# internal_excitation_-_8.net
KiCad netlist of a schematic drawn in EAGLE
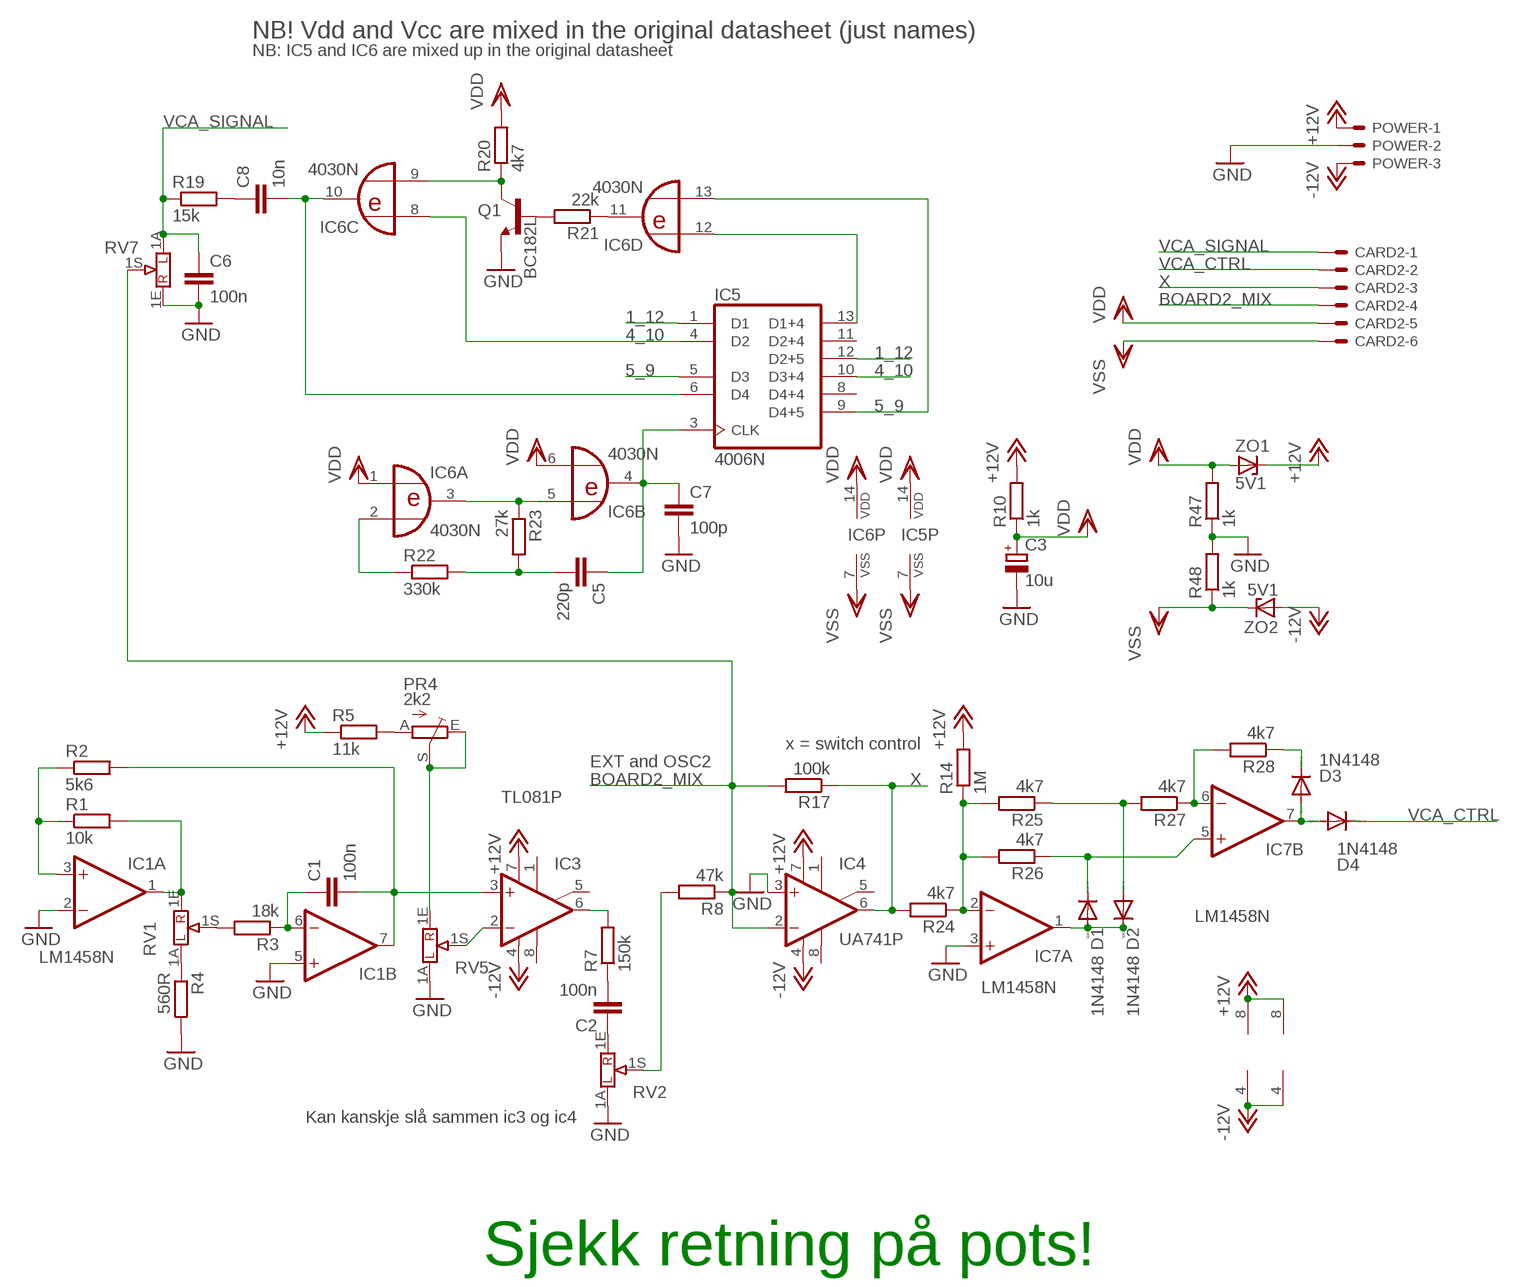
[diagram p0: schematic, sheet 1]

(export (version "E")
  (design (tool "Eeschema 10.0.6"))
  (components
    (comp (ref "C1")
      (value "100n")
      (footprint "eagle-import:C050-025X075")
      (libsource (lib "eagle-import") (part "C-EU050-025X075"))
    )
    (comp (ref "C2")
      (value "100n")
      (footprint "eagle-import:C025-025X050")
      (libsource (lib "eagle-import") (part "C-EU025-025X050"))
    )
    (comp (ref "C3")
      (value "10u")
      (footprint "eagle-import:E2,5-5")
      (libsource (lib "eagle-import") (part "CPOL-EUE2.5-5"))
    )
    (comp (ref "C5")
      (value "220p")
      (footprint "eagle-import:C025-025X050")
      (libsource (lib "eagle-import") (part "C-EU025-025X050"))
    )
    (comp (ref "C6")
      (value "100n")
      (footprint "eagle-import:C025-025X050")
      (libsource (lib "eagle-import") (part "C-EU025-025X050"))
    )
    (comp (ref "C7")
      (value "100p")
      (footprint "eagle-import:C025-025X050")
      (libsource (lib "eagle-import") (part "C-EU025-025X050"))
    )
    (comp (ref "C8")
      (value "10n")
      (footprint "eagle-import:C050-025X075")
      (libsource (lib "eagle-import") (part "C-EU050-025X075"))
    )
    (comp (ref "CARD2")
      (value "22-23-2061")
      (footprint "eagle-import:22-23-2061")
      (fields (field (name "MF") "MOLEX"))
      (libsource (lib "eagle-import") (part "22-23-2061"))
    )
    (comp (ref "D1")
      (value "1N4148")
      (footprint "eagle-import:DO35-5J")
      (libsource (lib "eagle-import") (part "1N4148DOJ35-5"))
    )
    (comp (ref "D2")
      (value "1N4148")
      (footprint "eagle-import:DO35-5J")
      (libsource (lib "eagle-import") (part "1N4148DOJ35-5"))
    )
    (comp (ref "D3")
      (value "1N4148")
      (footprint "eagle-import:DO35-5J")
      (libsource (lib "eagle-import") (part "1N4148DOJ35-5"))
    )
    (comp (ref "D4")
      (value "1N4148")
      (footprint "eagle-import:DO35-5J")
      (libsource (lib "eagle-import") (part "1N4148DOJ35-5"))
    )
    (comp (ref "IC1")
      (value "LM1458N")
      (footprint "eagle-import:DIL08")
      (libsource (lib "eagle-import") (part "1458NLM"))
    )
    (comp (ref "IC3")
      (value "TL081P")
      (footprint "eagle-import:DIL08")
      (libsource (lib "eagle-import") (part "TL081P"))
    )
    (comp (ref "IC4")
      (value "UA741P")
      (footprint "eagle-import:DIL08")
      (libsource (lib "eagle-import") (part "741PUA"))
    )
    (comp (ref "IC5")
      (value "4006N")
      (footprint "eagle-import:DIL14")
      (libsource (lib "eagle-import") (part "4006N"))
    )
    (comp (ref "IC6")
      (value "4030N")
      (footprint "eagle-import:DIL14")
      (libsource (lib "eagle-import") (part "4030N"))
    )
    (comp (ref "IC7")
      (value "LM1458N")
      (footprint "eagle-import:DIL08")
      (libsource (lib "eagle-import") (part "1458NLM"))
    )
    (comp (ref "POWER")
      (value "KK-156-3")
      (footprint "eagle-import:KK-156-3")
      (libsource (lib "eagle-import") (part "KK-156-3"))
    )
    (comp (ref "PR4")
      (value "2k2")
      (footprint "eagle-import:CA9V")
      (libsource (lib "eagle-import") (part "TRIM_EU-CA9V"))
    )
    (comp (ref "Q1")
      (value "BC182L")
      (footprint "eagle-import:TO92-ECB")
      (libsource (lib "eagle-import") (part "-NPN-TO92-ECB"))
    )
    (comp (ref "R1")
      (value "10k")
      (footprint "eagle-import:0207_7")
      (libsource (lib "eagle-import") (part "R-EU_0207/7"))
    )
    (comp (ref "R2")
      (value "5k6")
      (footprint "eagle-import:0207_7")
      (libsource (lib "eagle-import") (part "R-EU_0207/7"))
    )
    (comp (ref "R3")
      (value "18k")
      (footprint "eagle-import:0207_7")
      (libsource (lib "eagle-import") (part "R-EU_0207/7"))
    )
    (comp (ref "R4")
      (value "560R")
      (footprint "eagle-import:0207_7")
      (libsource (lib "eagle-import") (part "R-EU_0207/7"))
    )
    (comp (ref "R5")
      (value "11k")
      (footprint "eagle-import:0207_7")
      (libsource (lib "eagle-import") (part "R-EU_0207/7"))
    )
    (comp (ref "R7")
      (value "150k")
      (footprint "eagle-import:0207_7")
      (libsource (lib "eagle-import") (part "R-EU_0207/7"))
    )
    (comp (ref "R8")
      (value "47k")
      (footprint "eagle-import:0207_7")
      (libsource (lib "eagle-import") (part "R-EU_0207/7"))
    )
    (comp (ref "R10")
      (value "1k")
      (footprint "eagle-import:0207_7")
      (libsource (lib "eagle-import") (part "R-EU_0207/7"))
    )
    (comp (ref "R14")
      (value "1M")
      (footprint "eagle-import:0207_7")
      (libsource (lib "eagle-import") (part "R-EU_0207/7"))
    )
    (comp (ref "R17")
      (value "100k")
      (footprint "eagle-import:0207_7")
      (libsource (lib "eagle-import") (part "R-EU_0207/7"))
    )
    (comp (ref "R19")
      (value "15k")
      (footprint "eagle-import:0207_7")
      (libsource (lib "eagle-import") (part "R-EU_0207/7"))
    )
    (comp (ref "R20")
      (value "4k7")
      (footprint "eagle-import:0207_7")
      (libsource (lib "eagle-import") (part "R-EU_0207/7"))
    )
    (comp (ref "R21")
      (value "22k")
      (footprint "eagle-import:0207_7")
      (libsource (lib "eagle-import") (part "R-EU_0207/7"))
    )
    (comp (ref "R22")
      (value "330k")
      (footprint "eagle-import:0207_7")
      (libsource (lib "eagle-import") (part "R-EU_0207/7"))
    )
    (comp (ref "R23")
      (value "27k")
      (footprint "eagle-import:0207_7")
      (libsource (lib "eagle-import") (part "R-EU_0207/7"))
    )
    (comp (ref "R24")
      (value "4k7")
      (footprint "eagle-import:0207_7")
      (libsource (lib "eagle-import") (part "R-EU_0207/7"))
    )
    (comp (ref "R25")
      (value "4k7")
      (footprint "eagle-import:0207_7")
      (libsource (lib "eagle-import") (part "R-EU_0207/7"))
    )
    (comp (ref "R26")
      (value "4k7")
      (footprint "eagle-import:0207_7")
      (libsource (lib "eagle-import") (part "R-EU_0207/7"))
    )
    (comp (ref "R27")
      (value "4k7")
      (footprint "eagle-import:0207_7")
      (libsource (lib "eagle-import") (part "R-EU_0207/7"))
    )
    (comp (ref "R28")
      (value "4k7")
      (footprint "eagle-import:0207_7")
      (libsource (lib "eagle-import") (part "R-EU_0207/7"))
    )
    (comp (ref "R47")
      (value "1k")
      (footprint "eagle-import:0207_7")
      (libsource (lib "eagle-import") (part "R-EU_0207/7"))
    )
    (comp (ref "R48")
      (value "1k")
      (footprint "eagle-import:0207_7")
      (libsource (lib "eagle-import") (part "R-EU_0207/7"))
    )
    (comp (ref "RV1")
      (value "10k log")
      (footprint "eagle-import:POT16_W_BRACKET")
      (libsource (lib "eagle-import") (part "POT16_W_BRACKET{dblquote}{dblquote}"))
    )
    (comp (ref "RV2")
      (value "10k log")
      (footprint "eagle-import:POT16_W_BRACKET")
      (libsource (lib "eagle-import") (part "POT16_W_BRACKET{dblquote}{dblquote}"))
    )
    (comp (ref "RV5")
      (value "10k")
      (footprint "eagle-import:POT16_W_BRACKET")
      (libsource (lib "eagle-import") (part "POT16_W_BRACKET{dblquote}{dblquote}"))
    )
    (comp (ref "RV7")
      (value "10k")
      (footprint "eagle-import:POT16_W_BRACKET")
      (libsource (lib "eagle-import") (part "POT16_W_BRACKET{dblquote}{dblquote}"))
    )
    (comp (ref "ZO1")
      (value "5V1")
      (footprint "eagle-import:ZDIO-5")
      (libsource (lib "eagle-import") (part "ZENER-DIODEZD-5"))
    )
    (comp (ref "ZO2")
      (value "5V1")
      (footprint "eagle-import:ZDIO-5")
      (libsource (lib "eagle-import") (part "ZENER-DIODEZD-5"))
    )
  )
  (nets
    (net (code "1") (name "+12V") (class "Default")
      (node (ref "IC1") (pin "8") (pinfunction "V+_8") (pintype "power_in"))
      (node (ref "IC3") (pin "7") (pinfunction "V+_7") (pintype "power_in"))
      (node (ref "IC4") (pin "7") (pinfunction "V+_7") (pintype "power_in"))
      (node (ref "IC7") (pin "8") (pinfunction "V+_8") (pintype "power_in"))
      (node (ref "POWER") (pin "1") (pinfunction "S_1") (pintype "passive"))
      (node (ref "R10") (pin "2") (pinfunction "2_2") (pintype "passive"))
      (node (ref "R14") (pin "2") (pinfunction "2_2") (pintype "passive"))
      (node (ref "R5") (pin "1") (pinfunction "1_1") (pintype "passive"))
      (node (ref "ZO1") (pin "C") (pinfunction "C_C") (pintype "passive"))
    )
    (net (code "2") (name "-12V") (class "Default")
      (node (ref "IC1") (pin "4") (pinfunction "V-_4") (pintype "power_in"))
      (node (ref "IC3") (pin "4") (pinfunction "V-_4") (pintype "power_in"))
      (node (ref "IC4") (pin "4") (pinfunction "V-_4") (pintype "power_in"))
      (node (ref "IC7") (pin "4") (pinfunction "V-_4") (pintype "power_in"))
      (node (ref "POWER") (pin "3") (pinfunction "S_3") (pintype "passive"))
      (node (ref "ZO2") (pin "A") (pinfunction "A_A") (pintype "passive"))
    )
    (net (code "3") (name "/1_12") (class "Default")
      (node (ref "IC5") (pin "1") (pinfunction "D1_1") (pintype "input"))
      (node (ref "IC5") (pin "12") (pinfunction "D2+5_12") (pintype "output"))
    )
    (net (code "4") (name "/4_10") (class "Default")
      (node (ref "IC5") (pin "10") (pinfunction "D3+4_10") (pintype "output"))
      (node (ref "IC5") (pin "4") (pinfunction "D2_4") (pintype "input"))
      (node (ref "IC6") (pin "8") (pinfunction "I0_8") (pintype "input"))
    )
    (net (code "5") (name "/5_9") (class "Default")
      (node (ref "IC5") (pin "5") (pinfunction "D3_5") (pintype "input"))
      (node (ref "IC5") (pin "9") (pinfunction "D4+5_9") (pintype "output"))
      (node (ref "IC6") (pin "13") (pinfunction "I1_13") (pintype "input"))
    )
    (net (code "6") (name "/BOARD2_MIX") (class "Default")
      (node (ref "CARD2") (pin "4") (pinfunction "S_4") (pintype "passive"))
      (node (ref "IC4") (pin "2") (pinfunction "-IN_2") (pintype "input"))
      (node (ref "R17") (pin "2") (pinfunction "2_2") (pintype "passive"))
      (node (ref "R8") (pin "1") (pinfunction "1_1") (pintype "passive"))
      (node (ref "RV7") (pin "1S") (pinfunction "1S_1S") (pintype "passive"))
    )
    (net (code "7") (name "/VCA_CTRL") (class "Default")
      (node (ref "CARD2") (pin "2") (pinfunction "S_2") (pintype "passive"))
      (node (ref "D4") (pin "C") (pinfunction "C_C") (pintype "passive"))
    )
    (net (code "8") (name "/VCA_SIGNAL") (class "Default")
      (node (ref "C6") (pin "1") (pinfunction "1_1") (pintype "passive"))
      (node (ref "CARD2") (pin "1") (pinfunction "S_1") (pintype "passive"))
      (node (ref "R19") (pin "1") (pinfunction "1_1") (pintype "passive"))
      (node (ref "RV7") (pin "1A") (pinfunction "1A_1A") (pintype "passive"))
    )
    (net (code "9") (name "/X") (class "Default")
      (node (ref "CARD2") (pin "3") (pinfunction "S_3") (pintype "passive"))
      (node (ref "IC4") (pin "6") (pinfunction "OUT_6") (pintype "output"))
      (node (ref "R17") (pin "1") (pinfunction "1_1") (pintype "passive"))
      (node (ref "R24") (pin "2") (pinfunction "2_2") (pintype "passive"))
    )
    (net (code "10") (name "GND") (class "Default")
      (node (ref "C3") (pin "-") (pinfunction "-_-") (pintype "passive"))
      (node (ref "C6") (pin "2") (pinfunction "2_2") (pintype "passive"))
      (node (ref "C7") (pin "2") (pinfunction "2_2") (pintype "passive"))
      (node (ref "IC1") (pin "2") (pinfunction "-IN_2") (pintype "input"))
      (node (ref "IC1") (pin "5") (pinfunction "+IN_5") (pintype "input"))
      (node (ref "IC4") (pin "3") (pinfunction "+IN_3") (pintype "input"))
      (node (ref "IC7") (pin "3") (pinfunction "+IN_3") (pintype "input"))
      (node (ref "POWER") (pin "2") (pinfunction "S_2") (pintype "passive"))
      (node (ref "Q1") (pin "E") (pinfunction "E_E") (pintype "passive"))
      (node (ref "R4") (pin "2") (pinfunction "2_2") (pintype "passive"))
      (node (ref "R47") (pin "1") (pinfunction "1_1") (pintype "passive"))
      (node (ref "R48") (pin "2") (pinfunction "2_2") (pintype "passive"))
      (node (ref "RV2") (pin "1A") (pinfunction "1A_1A") (pintype "passive"))
      (node (ref "RV5") (pin "1A") (pinfunction "1A_1A") (pintype "passive"))
      (node (ref "RV7") (pin "1E") (pinfunction "1E_1E") (pintype "passive"))
    )
    (net (code "11") (name "Net-(C2-Pad1)") (class "Default")
      (node (ref "C2") (pin "1") (pinfunction "1_1") (pintype "passive"))
      (node (ref "RV2") (pin "1E") (pinfunction "1E_1E") (pintype "passive"))
    )
    (net (code "12") (name "Net-(C2-Pad2)") (class "Default")
      (node (ref "C2") (pin "2") (pinfunction "2_2") (pintype "passive"))
      (node (ref "R7") (pin "1") (pinfunction "1_1") (pintype "passive"))
    )
    (net (code "13") (name "Net-(C5-Pad2)") (class "Default")
      (node (ref "C5") (pin "2") (pinfunction "2_2") (pintype "passive"))
      (node (ref "R22") (pin "2") (pinfunction "2_2") (pintype "passive"))
      (node (ref "R23") (pin "2") (pinfunction "2_2") (pintype "passive"))
    )
    (net (code "14") (name "Net-(C8-Pad1)") (class "Default")
      (node (ref "C8") (pin "1") (pinfunction "1_1") (pintype "passive"))
      (node (ref "R19") (pin "2") (pinfunction "2_2") (pintype "passive"))
    )
    (net (code "15") (name "Net-(D2-PadA)") (class "Default")
      (node (ref "D2") (pin "A") (pinfunction "A_A") (pintype "passive"))
      (node (ref "R25") (pin "1") (pinfunction "1_1") (pintype "passive"))
      (node (ref "R27") (pin "2") (pinfunction "2_2") (pintype "passive"))
    )
    (net (code "16") (name "Net-(D3-PadC)") (class "Default")
      (node (ref "D3") (pin "C") (pinfunction "C_C") (pintype "passive"))
      (node (ref "R28") (pin "1") (pinfunction "1_1") (pintype "passive"))
    )
    (net (code "17") (name "Net-(IC1A-+IN)") (class "Default")
      (node (ref "IC1") (pin "3") (pinfunction "+IN_3") (pintype "input"))
      (node (ref "R1") (pin "1") (pinfunction "1_1") (pintype "passive"))
      (node (ref "R2") (pin "1") (pinfunction "1_1") (pintype "passive"))
    )
    (net (code "18") (name "Net-(IC1A-OUT)") (class "Default")
      (node (ref "IC1") (pin "1") (pinfunction "OUT_1") (pintype "output"))
      (node (ref "R1") (pin "2") (pinfunction "2_2") (pintype "passive"))
      (node (ref "RV1") (pin "1E") (pinfunction "1E_1E") (pintype "passive"))
    )
    (net (code "19") (name "Net-(IC1B--IN)") (class "Default")
      (node (ref "C1") (pin "1") (pinfunction "1_1") (pintype "passive"))
      (node (ref "IC1") (pin "6") (pinfunction "-IN_6") (pintype "input"))
      (node (ref "R3") (pin "1") (pinfunction "1_1") (pintype "passive"))
    )
    (net (code "20") (name "Net-(IC1B-OUT)") (class "Default")
      (node (ref "C1") (pin "2") (pinfunction "2_2") (pintype "passive"))
      (node (ref "IC1") (pin "7") (pinfunction "OUT_7") (pintype "output"))
      (node (ref "IC3") (pin "3") (pinfunction "+IN_3") (pintype "input"))
      (node (ref "R2") (pin "2") (pinfunction "2_2") (pintype "passive"))
    )
    (net (code "21") (name "Net-(IC3--IN)") (class "Default")
      (node (ref "IC3") (pin "2") (pinfunction "-IN_2") (pintype "input"))
      (node (ref "RV5") (pin "1S") (pinfunction "1S_1S") (pintype "passive"))
    )
    (net (code "22") (name "Net-(IC3-OUT)") (class "Default")
      (node (ref "IC3") (pin "6") (pinfunction "OUT_6") (pintype "output"))
      (node (ref "R7") (pin "2") (pinfunction "2_2") (pintype "passive"))
    )
    (net (code "23") (name "Net-(IC5A-CLK)") (class "Default")
      (node (ref "C5") (pin "1") (pinfunction "1_1") (pintype "passive"))
      (node (ref "C7") (pin "1") (pinfunction "1_1") (pintype "passive"))
      (node (ref "IC5") (pin "3") (pinfunction "CLK_3") (pintype "input"))
      (node (ref "IC6") (pin "4") (pinfunction "O_4") (pintype "output"))
    )
    (net (code "24") (name "Net-(IC5A-D1+4)") (class "Default")
      (node (ref "IC5") (pin "13") (pinfunction "D1+4_13") (pintype "output"))
      (node (ref "IC6") (pin "12") (pinfunction "I0_12") (pintype "input"))
    )
    (net (code "25") (name "Net-(IC5A-D4)") (class "Default")
      (node (ref "C8") (pin "2") (pinfunction "2_2") (pintype "passive"))
      (node (ref "IC5") (pin "6") (pinfunction "D4_6") (pintype "input"))
      (node (ref "IC6") (pin "10") (pinfunction "O_10") (pintype "output"))
    )
    (net (code "26") (name "Net-(IC6A-I1)") (class "Default")
      (node (ref "IC6") (pin "2") (pinfunction "I1_2") (pintype "input"))
      (node (ref "R22") (pin "1") (pinfunction "1_1") (pintype "passive"))
    )
    (net (code "27") (name "Net-(IC6A-O)") (class "Default")
      (node (ref "IC6") (pin "3") (pinfunction "O_3") (pintype "output"))
      (node (ref "IC6") (pin "5") (pinfunction "I0_5") (pintype "input"))
      (node (ref "R23") (pin "1") (pinfunction "1_1") (pintype "passive"))
    )
    (net (code "28") (name "Net-(IC6C-I1)") (class "Default")
      (node (ref "IC6") (pin "9") (pinfunction "I1_9") (pintype "input"))
      (node (ref "Q1") (pin "C") (pinfunction "C_C") (pintype "passive"))
      (node (ref "R20") (pin "1") (pinfunction "1_1") (pintype "passive"))
    )
    (net (code "29") (name "Net-(IC6D-O)") (class "Default")
      (node (ref "IC6") (pin "11") (pinfunction "O_11") (pintype "output"))
      (node (ref "R21") (pin "1") (pinfunction "1_1") (pintype "passive"))
    )
    (net (code "30") (name "Net-(IC7A--IN)") (class "Default")
      (node (ref "IC7") (pin "2") (pinfunction "-IN_2") (pintype "input"))
      (node (ref "R14") (pin "1") (pinfunction "1_1") (pintype "passive"))
      (node (ref "R24") (pin "1") (pinfunction "1_1") (pintype "passive"))
      (node (ref "R25") (pin "2") (pinfunction "2_2") (pintype "passive"))
      (node (ref "R26") (pin "2") (pinfunction "2_2") (pintype "passive"))
    )
    (net (code "31") (name "Net-(IC7A-OUT)") (class "Default")
      (node (ref "D1") (pin "A") (pinfunction "A_A") (pintype "passive"))
      (node (ref "D2") (pin "C") (pinfunction "C_C") (pintype "passive"))
      (node (ref "IC7") (pin "1") (pinfunction "OUT_1") (pintype "output"))
    )
    (net (code "32") (name "Net-(IC7B-+IN)") (class "Default")
      (node (ref "D1") (pin "C") (pinfunction "C_C") (pintype "passive"))
      (node (ref "IC7") (pin "5") (pinfunction "+IN_5") (pintype "input"))
      (node (ref "R26") (pin "1") (pinfunction "1_1") (pintype "passive"))
    )
    (net (code "33") (name "Net-(IC7B--IN)") (class "Default")
      (node (ref "IC7") (pin "6") (pinfunction "-IN_6") (pintype "input"))
      (node (ref "R27") (pin "1") (pinfunction "1_1") (pintype "passive"))
      (node (ref "R28") (pin "2") (pinfunction "2_2") (pintype "passive"))
    )
    (net (code "34") (name "Net-(IC7B-OUT)") (class "Default")
      (node (ref "D3") (pin "A") (pinfunction "A_A") (pintype "passive"))
      (node (ref "D4") (pin "A") (pinfunction "A_A") (pintype "passive"))
      (node (ref "IC7") (pin "7") (pinfunction "OUT_7") (pintype "output"))
    )
    (net (code "35") (name "Net-(PR4-PadA)") (class "Default")
      (node (ref "PR4") (pin "A") (pinfunction "A_A") (pintype "passive"))
      (node (ref "R5") (pin "2") (pinfunction "2_2") (pintype "passive"))
    )
    (net (code "36") (name "Net-(PR4-PadE)") (class "Default")
      (node (ref "PR4") (pin "E") (pinfunction "E_E") (pintype "passive"))
      (node (ref "PR4") (pin "S") (pinfunction "S_S") (pintype "passive"))
      (node (ref "RV5") (pin "1E") (pinfunction "1E_1E") (pintype "passive"))
    )
    (net (code "37") (name "Net-(Q1-PadB)") (class "Default")
      (node (ref "Q1") (pin "B") (pinfunction "B_B") (pintype "passive"))
      (node (ref "R21") (pin "2") (pinfunction "2_2") (pintype "passive"))
    )
    (net (code "38") (name "Net-(R3-Pad2)") (class "Default")
      (node (ref "R3") (pin "2") (pinfunction "2_2") (pintype "passive"))
      (node (ref "RV1") (pin "1S") (pinfunction "1S_1S") (pintype "passive"))
    )
    (net (code "39") (name "Net-(R4-Pad1)") (class "Default")
      (node (ref "R4") (pin "1") (pinfunction "1_1") (pintype "passive"))
      (node (ref "RV1") (pin "1A") (pinfunction "1A_1A") (pintype "passive"))
    )
    (net (code "40") (name "Net-(R8-Pad2)") (class "Default")
      (node (ref "R8") (pin "2") (pinfunction "2_2") (pintype "passive"))
      (node (ref "RV2") (pin "1S") (pinfunction "1S_1S") (pintype "passive"))
    )
    (net (code "41") (name "VDD") (class "Default")
      (node (ref "C3") (pin "+") (pinfunction "+_+") (pintype "passive"))
      (node (ref "CARD2") (pin "5") (pinfunction "S_5") (pintype "passive"))
      (node (ref "IC5") (pin "14") (pinfunction "VDD_14") (pintype "power_in"))
      (node (ref "IC6") (pin "1") (pinfunction "I0_1") (pintype "input"))
      (node (ref "IC6") (pin "14") (pinfunction "VDD_14") (pintype "power_in"))
      (node (ref "IC6") (pin "6") (pinfunction "I1_6") (pintype "input"))
      (node (ref "R10") (pin "1") (pinfunction "1_1") (pintype "passive"))
      (node (ref "R20") (pin "2") (pinfunction "2_2") (pintype "passive"))
      (node (ref "R47") (pin "2") (pinfunction "2_2") (pintype "passive"))
      (node (ref "ZO1") (pin "A") (pinfunction "A_A") (pintype "passive"))
    )
    (net (code "42") (name "VSS") (class "Default")
      (node (ref "CARD2") (pin "6") (pinfunction "S_6") (pintype "passive"))
      (node (ref "IC5") (pin "7") (pinfunction "VSS_7") (pintype "power_in"))
      (node (ref "IC6") (pin "7") (pinfunction "VSS_7") (pintype "power_in"))
      (node (ref "R48") (pin "1") (pinfunction "1_1") (pintype "passive"))
      (node (ref "ZO2") (pin "C") (pinfunction "C_C") (pintype "passive"))
    )
    (net (code "43") (name "unconnected-(IC3-ON1-Pad1)") (class "Default")
      (node (ref "IC3") (pin "1") (pinfunction "ON1_1") (pintype "passive"))
    )
    (net (code "44") (name "unconnected-(IC3-ON2-Pad5)") (class "Default")
      (node (ref "IC3") (pin "5") (pinfunction "ON2_5") (pintype "passive"))
    )
    (net (code "45") (name "unconnected-(IC3-OPT-Pad8)") (class "Default")
      (node (ref "IC3") (pin "8") (pinfunction "OPT_8") (pintype "passive"))
    )
    (net (code "46") (name "unconnected-(IC4-ON1-Pad1)") (class "Default")
      (node (ref "IC4") (pin "1") (pinfunction "ON1_1") (pintype "passive"))
    )
    (net (code "47") (name "unconnected-(IC4-ON2-Pad5)") (class "Default")
      (node (ref "IC4") (pin "5") (pinfunction "ON2_5") (pintype "passive"))
    )
    (net (code "48") (name "unconnected-(IC4-OPT-Pad8)") (class "Default")
      (node (ref "IC4") (pin "8") (pinfunction "OPT_8") (pintype "passive"))
    )
    (net (code "49") (name "unconnected-(IC5A-D2+4-Pad11)") (class "Default")
      (node (ref "IC5") (pin "11") (pinfunction "D2+4_11") (pintype "output"))
    )
    (net (code "50") (name "unconnected-(IC5A-D4+4-Pad8)") (class "Default")
      (node (ref "IC5") (pin "8") (pinfunction "D4+4_8") (pintype "output"))
    )
  )
)
